# PHY.net
KiCad netlist of a schematic drawn in Altium Designer
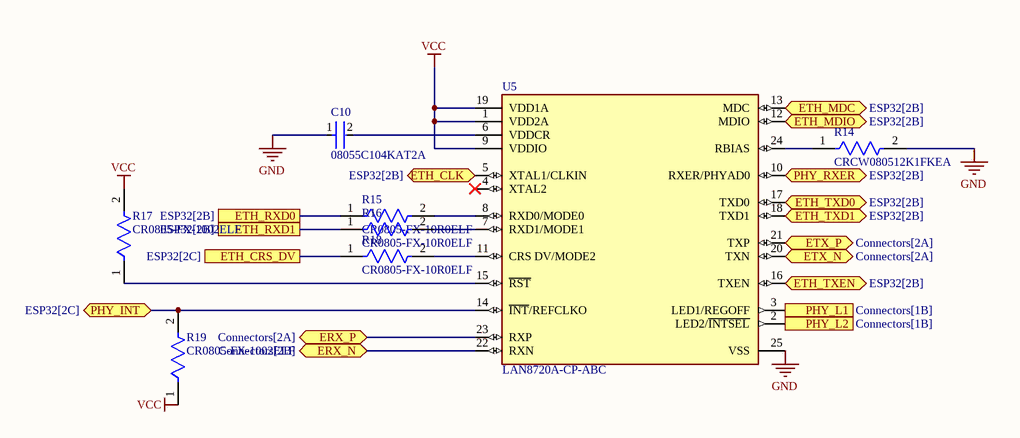
[diagram p0: PHY.SchDoc]

(export (version "E")
  (design (tool "Eeschema 10.0.6"))
  (components
    (comp (ref "C10")
      (value "08055C104KAT2A")
      (footprint "FP-0805-L_2_01_0_2-W_1_25-IPC_C")
      (description "General Purpose Ceramic Capacitor, 0805, 100nF, 10%, X7R, 0.15, 50V")
      (fields (field (name "TOLERANCE") "10%") (field (name "VOLTAGE") "50V"))
      (libsource (lib "Altium Content Vault") (part "02cd4be3c70576c341d710602a673aa"))
    )
    (comp (ref "R14")
      (value "CRCW080512K1FKEA")
      (footprint "FP-CRCW0805-e3-IPC_B")
      (description "RES Thick Film, 12.1kΩ, 1%, 0.125W, 100ppm/°C, 0805")
      (fields (field (name "TOLERANCE") "1%"))
      (libsource (lib "Altium Content Vault") (part "1029c3af85768c4190bb7ad29bc67b5"))
    )
    (comp (ref "R15")
      (value "CR0805-FX-10R0ELF")
      (footprint "FP-CR0805-IPC_B")
      (description "Thick Film Chip Resistors 0805 10Ω 0.125W 1% 100ppm/°C")
      (fields (field (name "TOLERANCE") "1%"))
      (libsource (lib "Altium Content Vault") (part "1029c3af85768c4190bb7ad29bc67b5"))
    )
    (comp (ref "R16")
      (value "CR0805-FX-10R0ELF")
      (footprint "FP-CR0805-IPC_B")
      (description "Thick Film Chip Resistors 0805 10Ω 0.125W 1% 100ppm/°C")
      (fields (field (name "TOLERANCE") "1%"))
      (libsource (lib "Altium Content Vault") (part "1029c3af85768c4190bb7ad29bc67b5"))
    )
    (comp (ref "R17")
      (value "CR0805-FX-1002ELF")
      (footprint "FP-CR0805-IPC_A")
      (description "Thick Film Chip Resistors 0805 10kΩ 0.125W 1% 100ppm/°C")
      (fields (field (name "TOLERANCE") "1%"))
      (libsource (lib "Altium Content Vault") (part "1029c3af85768c4190bb7ad29bc67b5"))
    )
    (comp (ref "R18")
      (value "CR0805-FX-10R0ELF")
      (footprint "FP-CR0805-IPC_B")
      (description "Thick Film Chip Resistors 0805 10Ω 0.125W 1% 100ppm/°C")
      (fields (field (name "TOLERANCE") "1%"))
      (libsource (lib "Altium Content Vault") (part "1029c3af85768c4190bb7ad29bc67b5"))
    )
    (comp (ref "R19")
      (value "CR0805-FX-1002ELF")
      (footprint "FP-CR0805-IPC_A")
      (description "Thick Film Chip Resistors 0805 10kΩ 0.125W 1% 100ppm/°C")
      (fields (field (name "TOLERANCE") "1%"))
      (libsource (lib "Altium Content Vault") (part "1029c3af85768c4190bb7ad29bc67b5"))
    )
    (comp (ref "U5")
      (value "LAN8720A-CP-ABC")
      (footprint "FP-24-S4QFN-4x4B-0_5P-IPC_B")
      (description "IC TRANSCEIVER FULL 2/2 24SQFN")
      (libsource (lib "Altium Content Vault") (part "85d2e6b3fccd3bdbf69e837699e532a"))
    )
  )
  (nets
    (net (code "1") (name "/ERX_N") (class "Default")
      (node (ref "U5") (pin "22") (pinfunction "RXN_22") (pintype "bidirectional"))
    )
    (net (code "2") (name "/ERX_P") (class "Default")
      (node (ref "U5") (pin "23") (pinfunction "RXP_23") (pintype "bidirectional"))
    )
    (net (code "3") (name "/ETH_CLK") (class "Default")
      (node (ref "U5") (pin "5") (pinfunction "XTAL1/CLKIN_5") (pintype "bidirectional"))
    )
    (net (code "4") (name "/ETH_CRS_DV") (class "Default")
      (node (ref "R18") (pin "1") (pinfunction "1_1") (pintype "passive"))
    )
    (net (code "5") (name "/ETH_MDC") (class "Default")
      (node (ref "U5") (pin "13") (pinfunction "MDC_13") (pintype "bidirectional"))
    )
    (net (code "6") (name "/ETH_MDIO") (class "Default")
      (node (ref "U5") (pin "12") (pinfunction "MDIO_12") (pintype "bidirectional"))
    )
    (net (code "7") (name "/ETH_RXD0") (class "Default")
      (node (ref "R15") (pin "1") (pinfunction "1_1") (pintype "passive"))
    )
    (net (code "8") (name "/ETH_RXD1") (class "Default")
      (node (ref "R16") (pin "1") (pinfunction "1_1") (pintype "passive"))
    )
    (net (code "9") (name "/ETH_TXD0") (class "Default")
      (node (ref "U5") (pin "17") (pinfunction "TXD0_17") (pintype "bidirectional"))
    )
    (net (code "10") (name "/ETH_TXD1") (class "Default")
      (node (ref "U5") (pin "18") (pinfunction "TXD1_18") (pintype "bidirectional"))
    )
    (net (code "11") (name "/ETH_TXEN") (class "Default")
      (node (ref "U5") (pin "16") (pinfunction "TXEN_16") (pintype "bidirectional"))
    )
    (net (code "12") (name "/ETX_N") (class "Default")
      (node (ref "U5") (pin "20") (pinfunction "TXN_20") (pintype "bidirectional"))
    )
    (net (code "13") (name "/ETX_P") (class "Default")
      (node (ref "U5") (pin "21") (pinfunction "TXP_21") (pintype "bidirectional"))
    )
    (net (code "14") (name "/PHY_INT") (class "Default")
      (node (ref "R19") (pin "2") (pinfunction "2_2") (pintype "passive"))
      (node (ref "U5") (pin "14") (pinfunction "~{INT}/REFCLKO_14") (pintype "bidirectional"))
    )
    (net (code "15") (name "/PHY_L1") (class "Default")
      (node (ref "U5") (pin "3") (pinfunction "LED1/REGOFF_3") (pintype "output"))
    )
    (net (code "16") (name "/PHY_L2") (class "Default")
      (node (ref "U5") (pin "2") (pinfunction "LED2/~{INTSEL}_2") (pintype "output"))
    )
    (net (code "17") (name "/PHY_RXER") (class "Default")
      (node (ref "U5") (pin "10") (pinfunction "RXER/PHYAD0_10") (pintype "bidirectional"))
    )
    (net (code "18") (name "GND") (class "Default")
      (node (ref "C10") (pin "1") (pinfunction "1_1") (pintype "passive"))
      (node (ref "R14") (pin "2") (pinfunction "2_2") (pintype "passive"))
      (node (ref "U5") (pin "25") (pinfunction "VSS_25") (pintype "power_in"))
    )
    (net (code "19") (name "Net-(U5-CRS_DV{slash}MODE2)") (class "Default")
      (node (ref "R18") (pin "2") (pinfunction "2_2") (pintype "passive"))
      (node (ref "U5") (pin "11") (pinfunction "CRS_DV/MODE2_11") (pintype "bidirectional"))
    )
    (net (code "20") (name "Net-(U5-RBIAS)") (class "Default")
      (node (ref "R14") (pin "1") (pinfunction "1_1") (pintype "passive"))
      (node (ref "U5") (pin "24") (pinfunction "RBIAS_24") (pintype "bidirectional"))
    )
    (net (code "21") (name "Net-(U5-RXD0{slash}MODE0)") (class "Default")
      (node (ref "R15") (pin "2") (pinfunction "2_2") (pintype "passive"))
      (node (ref "U5") (pin "8") (pinfunction "RXD0/MODE0_8") (pintype "bidirectional"))
    )
    (net (code "22") (name "Net-(U5-RXD1{slash}MODE1)") (class "Default")
      (node (ref "R16") (pin "2") (pinfunction "2_2") (pintype "passive"))
      (node (ref "U5") (pin "7") (pinfunction "RXD1/MODE1_7") (pintype "bidirectional"))
    )
    (net (code "23") (name "Net-(U5-VDDCR)") (class "Default")
      (node (ref "C10") (pin "2") (pinfunction "2_2") (pintype "passive"))
      (node (ref "U5") (pin "6") (pinfunction "VDDCR_6") (pintype "power_in"))
    )
    (net (code "24") (name "Net-(U5-~{RST})") (class "Default")
      (node (ref "R17") (pin "1") (pinfunction "1_1") (pintype "passive"))
      (node (ref "U5") (pin "15") (pinfunction "~{RST}_15") (pintype "bidirectional"))
    )
    (net (code "25") (name "VCC") (class "Default")
      (node (ref "R17") (pin "2") (pinfunction "2_2") (pintype "passive"))
      (node (ref "R19") (pin "1") (pinfunction "1_1") (pintype "passive"))
      (node (ref "U5") (pin "1") (pinfunction "VDD2A_1") (pintype "power_in"))
      (node (ref "U5") (pin "19") (pinfunction "VDD1A_19") (pintype "power_in"))
      (node (ref "U5") (pin "9") (pinfunction "VDDIO_9") (pintype "power_in"))
    )
    (net (code "26") (name "unconnected-(U5-XTAL2-Pad4)") (class "Default")
      (node (ref "U5") (pin "4") (pinfunction "XTAL2_4") (pintype "bidirectional+no_connect"))
    )
  )
)
